# openSX70-dongle-USB-V2.net
KiCad netlist of a schematic drawn in EAGLE
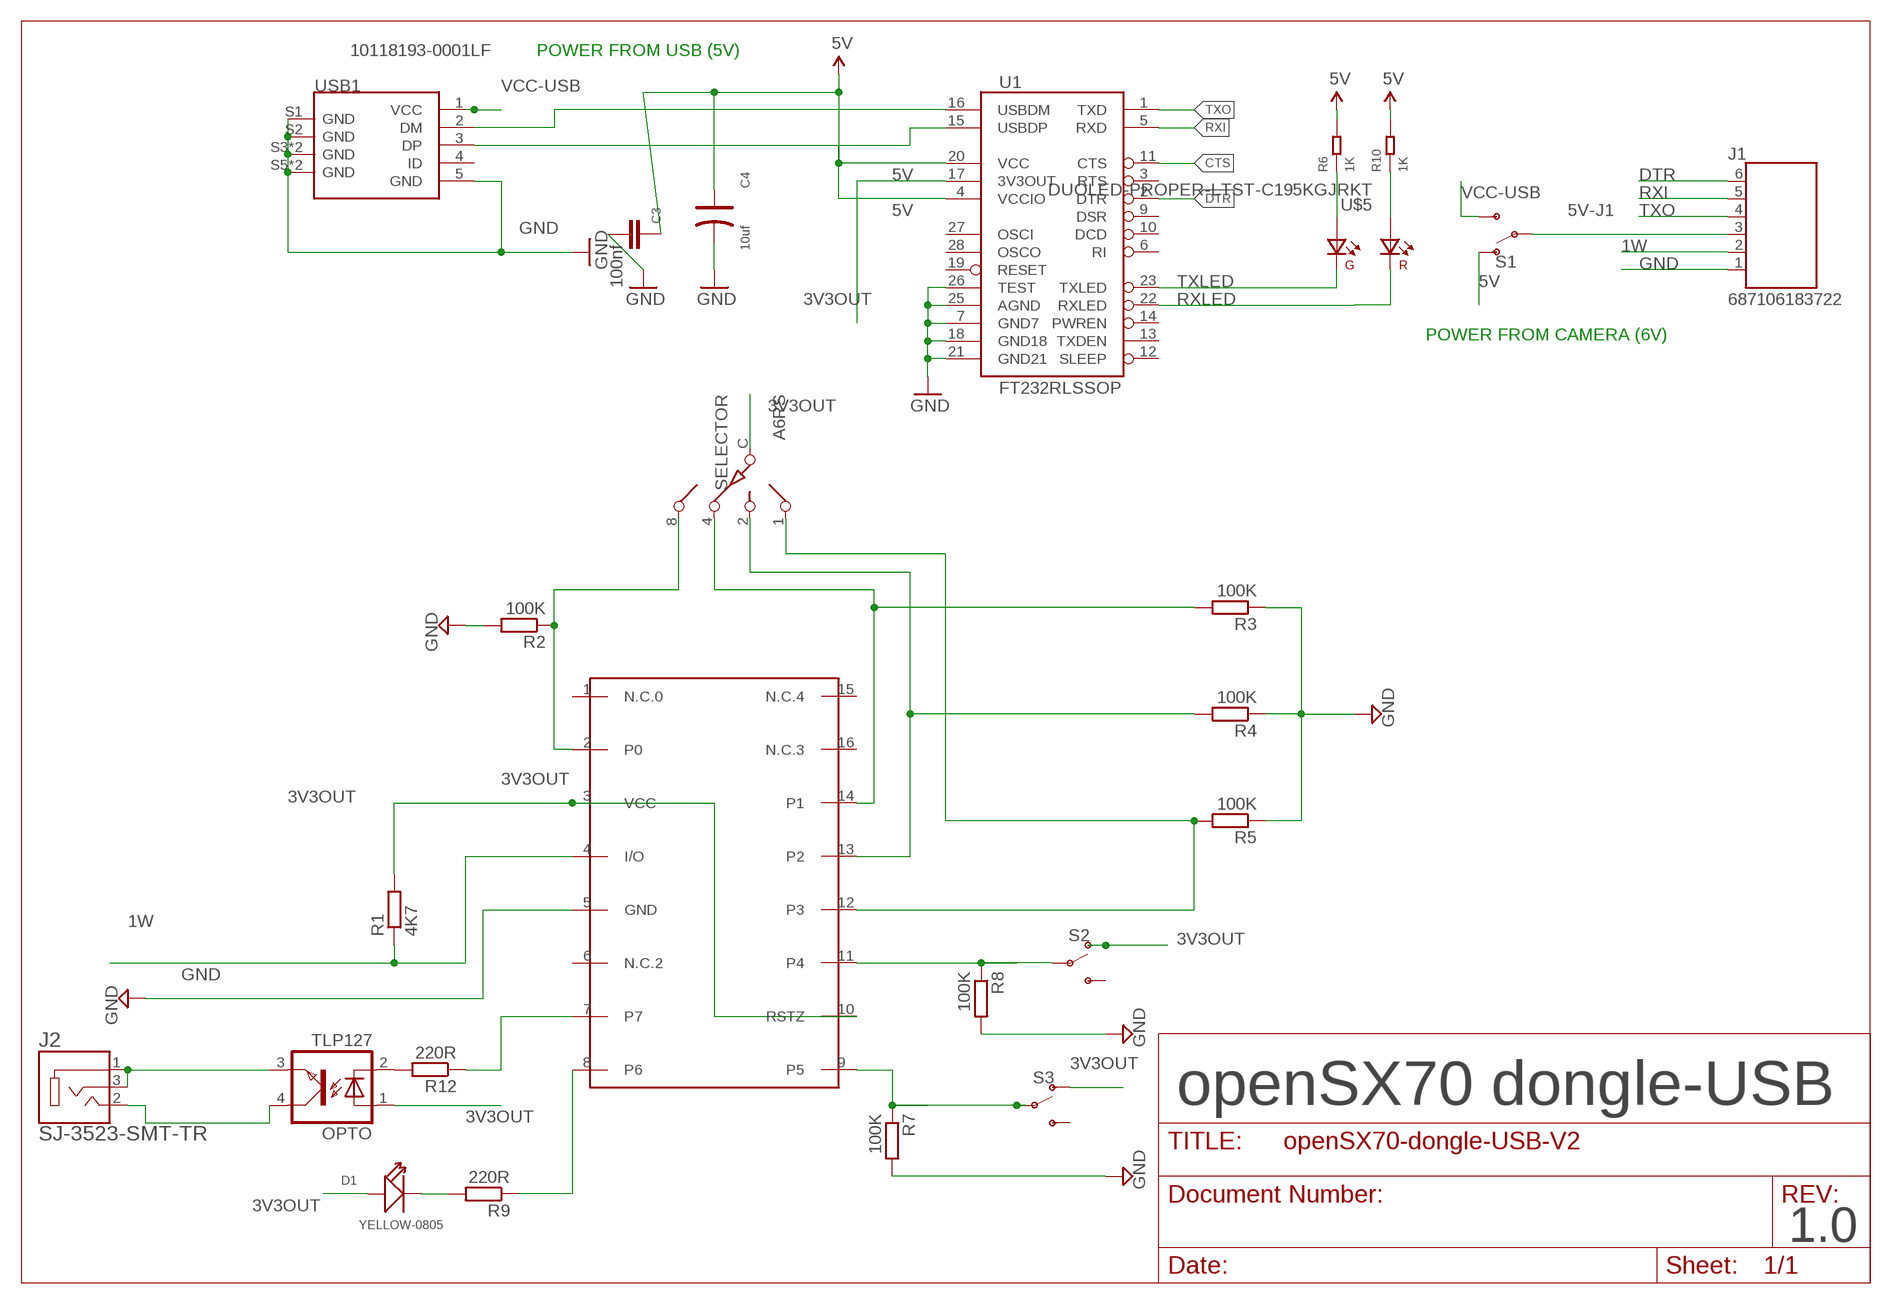
[diagram p0: schematic, sheet 1]

(export (version "E")
  (design (tool "Eeschema 10.0.6"))
  (components
    (comp (ref "C3")
      (value "100nf")
      (footprint "eagle-import:C0603")
      (libsource (lib "eagle-import") (part "C-EUC0603"))
    )
    (comp (ref "C4")
      (value "10uf")
      (footprint "eagle-import:AVX-A")
      (fields (field (name "MPN") "TAJA106K016RNJ"))
      (libsource (lib "eagle-import") (part "TANTALUM-SMD-10UF-16V-10%(AVX-A)"))
    )
    (comp (ref "D1")
      (value "YELLOW-0805")
      (footprint "eagle-import:LED-0805")
      (fields (field (name "MPN") "17-215UYC/S530-A3/TR8"))
      (libsource (lib "eagle-import") (part "SMD-LED-CLEAR-YELLOW(0805)"))
    )
    (comp (ref "DS2408")
      (value "DS2408")
      (footprint "eagle-import:SO16")
      (libsource (lib "eagle-import") (part "DS2408"))
    )
    (comp (ref "J1")
      (value "687106183722")
      (footprint "eagle-import:687106183722")
      (fields (field (name "MF") "Wurth Electronics"))
      (libsource (lib "eagle-import") (part "687106183722"))
    )
    (comp (ref "J2")
      (value "SJ-3523-SMT-TR")
      (footprint "eagle-import:CUI_SJ-3523-SMT-TR")
      (fields (field (name "MF") "CUI Inc."))
      (libsource (lib "eagle-import") (part "SJ-3523-SMT-TR"))
    )
    (comp (ref "OPTO")
      (value "TLP127")
      (footprint "eagle-import:SO-4")
      (libsource (lib "eagle-import") (part "TLP127"))
    )
    (comp (ref "R1")
      (value "4K7")
      (footprint "eagle-import:R0603")
      (libsource (lib "eagle-import") (part "R-EU_R0603"))
    )
    (comp (ref "R2")
      (value "100K")
      (footprint "eagle-import:R0603")
      (libsource (lib "eagle-import") (part "R-EU_R0603"))
    )
    (comp (ref "R3")
      (value "100K")
      (footprint "eagle-import:R0603")
      (libsource (lib "eagle-import") (part "R-EU_R0603"))
    )
    (comp (ref "R4")
      (value "100K")
      (footprint "eagle-import:R0603")
      (libsource (lib "eagle-import") (part "R-EU_R0603"))
    )
    (comp (ref "R5")
      (value "100K")
      (footprint "eagle-import:R0603")
      (libsource (lib "eagle-import") (part "R-EU_R0603"))
    )
    (comp (ref "R6")
      (value "1K")
      (footprint "eagle-import:R0603")
      (fields (field (name "MPN") "RC0603FR-071KL"))
      (libsource (lib "eagle-import") (part "SMD-RES-1K-1%-1/10W(0603)"))
    )
    (comp (ref "R7")
      (value "100K")
      (footprint "eagle-import:R0603")
      (libsource (lib "eagle-import") (part "R-EU_R0603"))
    )
    (comp (ref "R8")
      (value "100K")
      (footprint "eagle-import:R0603")
      (libsource (lib "eagle-import") (part "R-EU_R0603"))
    )
    (comp (ref "R9")
      (value "220R")
      (footprint "eagle-import:R0603")
      (libsource (lib "eagle-import") (part "R-EU_R0603"))
    )
    (comp (ref "R10")
      (value "1K")
      (footprint "eagle-import:R0603")
      (fields (field (name "MPN") "RC0603FR-071KL"))
      (libsource (lib "eagle-import") (part "SMD-RES-1K-1%-1/10W(0603)"))
    )
    (comp (ref "R12")
      (value "220R")
      (footprint "eagle-import:R0603")
      (libsource (lib "eagle-import") (part "R-EU_R0603"))
    )
    (comp (ref "S1")
      (value "SWITCH-SPDT-SMD-RIGHT-ANGLE")
      (footprint "eagle-import:SWITCH_SPST_SMD_A")
      (libsource (lib "eagle-import") (part "SWITCH-SPDT-SMD-RIGHT-ANGLE"))
    )
    (comp (ref "S2")
      (value "SWITCH-SPDT-SMD-RIGHT-ANGLE")
      (footprint "eagle-import:SWITCH_SPST_SMD_A")
      (libsource (lib "eagle-import") (part "SWITCH-SPDT-SMD-RIGHT-ANGLE"))
    )
    (comp (ref "S3")
      (value "SWITCH-SPDT-SMD-RIGHT-ANGLE")
      (footprint "eagle-import:SWITCH_SPST_SMD_A")
      (libsource (lib "eagle-import") (part "SWITCH-SPDT-SMD-RIGHT-ANGLE"))
    )
    (comp (ref "SELECTOR")
      (value "A6RS")
      (footprint "eagle-import:A6RS-161RS")
      (libsource (lib "eagle-import") (part "A6RS"))
    )
    (comp (ref "U$5")
      (value "DUOLED-PROPER-LTST-C195KGJRKT")
      (footprint "eagle-import:LTST-BILED-15X16")
      (fields (field (name "MF") "Lite-On Inc.") (field (name "MP") "LTST-C195KGJRKT"))
      (libsource (lib "eagle-import") (part "DUOLED-PROPER-LTST-C195KGJRKT"))
    )
    (comp (ref "U1")
      (value "FT232RLSSOP")
      (footprint "eagle-import:SSOP28DB")
      (libsource (lib "eagle-import") (part "FT232RLSSOP"))
    )
    (comp (ref "USB1")
      (value "10118193-0001LF")
      (footprint "eagle-import:MICRO-USB5+6P-SMD-0.65-B")
      (libsource (lib "eagle-import") (part "MICRO-USB-SMD-B-(10118193-0001LF)"))
    )
  )
  (nets
    (net (code "1") (name "/1W") (class "Default")
      (node (ref "DS2408") (pin "4") (pinfunction "I/O_4") (pintype "bidirectional"))
      (node (ref "J1") (pin "2") (pinfunction "5_2") (pintype "passive"))
      (node (ref "R1") (pin "1") (pinfunction "1_1") (pintype "passive"))
    )
    (net (code "2") (name "/3V3OUT") (class "Default")
      (node (ref "D1") (pin "+") (pinfunction "+_+") (pintype "passive"))
      (node (ref "DS2408") (pin "10") (pinfunction "RSTZ_10") (pintype "bidirectional"))
      (node (ref "DS2408") (pin "3") (pinfunction "VCC_3") (pintype "bidirectional"))
      (node (ref "OPTO") (pin "1") (pinfunction "A_1") (pintype "passive"))
      (node (ref "R1") (pin "2") (pinfunction "2_2") (pintype "passive"))
      (node (ref "S2") (pin "1") (pinfunction "O_1") (pintype "passive"))
      (node (ref "S3") (pin "1") (pinfunction "O_1") (pintype "passive"))
      (node (ref "SELECTOR") (pin "C") (pinfunction "C_C") (pintype "passive"))
      (node (ref "U1") (pin "17") (pinfunction "3V3OUT_17") (pintype "output"))
    )
    (net (code "3") (name "/5V-J1") (class "Default")
      (node (ref "J1") (pin "3") (pinfunction "4_3") (pintype "passive"))
      (node (ref "S1") (pin "2") (pinfunction "P_2") (pintype "passive"))
    )
    (net (code "4") (name "/RXLED") (class "Default")
      (node (ref "U$5") (pin "P$4") (pinfunction "K2_P$4") (pintype "passive"))
      (node (ref "U1") (pin "22") (pinfunction "RXLED_22") (pintype "input"))
    )
    (net (code "5") (name "/TXLED") (class "Default")
      (node (ref "U$5") (pin "P$3") (pinfunction "K1_P$3") (pintype "passive"))
      (node (ref "U1") (pin "23") (pinfunction "TXLED_23") (pintype "input"))
    )
    (net (code "6") (name "/VCC-USB") (class "Default")
      (node (ref "S1") (pin "3") (pinfunction "S_3") (pintype "passive"))
      (node (ref "USB1") (pin "1") (pinfunction "VCC_1") (pintype "bidirectional"))
    )
    (net (code "7") (name "5V") (class "Default")
      (node (ref "C3") (pin "1") (pinfunction "1_1") (pintype "passive"))
      (node (ref "C4") (pin "+") (pinfunction "+_+") (pintype "passive"))
      (node (ref "R10") (pin "2") (pinfunction "2_2") (pintype "passive"))
      (node (ref "R6") (pin "2") (pinfunction "2_2") (pintype "passive"))
      (node (ref "S1") (pin "1") (pinfunction "O_1") (pintype "passive"))
      (node (ref "U1") (pin "20") (pinfunction "VCC_20") (pintype "power_in"))
      (node (ref "U1") (pin "4") (pinfunction "VCCIO_4") (pintype "power_in"))
    )
    (net (code "8") (name "CTS") (class "Default")
      (node (ref "U1") (pin "11") (pinfunction "CTS_11") (pintype "input"))
    )
    (net (code "9") (name "DTR") (class "Default")
      (node (ref "J1") (pin "6") (pinfunction "1_6") (pintype "passive"))
      (node (ref "U1") (pin "2") (pinfunction "DTR_2") (pintype "output"))
    )
    (net (code "10") (name "GND") (class "Default")
      (node (ref "C3") (pin "2") (pinfunction "2_2") (pintype "passive"))
      (node (ref "C4") (pin "-") (pinfunction "-_-") (pintype "passive"))
      (node (ref "DS2408") (pin "5") (pinfunction "GND_5") (pintype "bidirectional"))
      (node (ref "J1") (pin "1") (pinfunction "6_1") (pintype "passive"))
      (node (ref "R2") (pin "2") (pinfunction "2_2") (pintype "passive"))
      (node (ref "R3") (pin "1") (pinfunction "1_1") (pintype "passive"))
      (node (ref "R4") (pin "1") (pinfunction "1_1") (pintype "passive"))
      (node (ref "R5") (pin "1") (pinfunction "1_1") (pintype "passive"))
      (node (ref "R7") (pin "2") (pinfunction "2_2") (pintype "passive"))
      (node (ref "R8") (pin "2") (pinfunction "2_2") (pintype "passive"))
      (node (ref "U1") (pin "18") (pinfunction "GND18_18") (pintype "power_in"))
      (node (ref "U1") (pin "21") (pinfunction "GND21_21") (pintype "power_in"))
      (node (ref "U1") (pin "25") (pinfunction "AGND_25") (pintype "power_in"))
      (node (ref "U1") (pin "26") (pinfunction "TEST_26") (pintype "input"))
      (node (ref "U1") (pin "7") (pinfunction "GND7_7") (pintype "power_in"))
      (node (ref "USB1") (pin "5") (pinfunction "GND_5") (pintype "bidirectional"))
      (node (ref "USB1") (pin "S1") (pinfunction "GND_S1") (pintype "bidirectional"))
      (node (ref "USB1") (pin "S2") (pinfunction "GND_S2") (pintype "bidirectional"))
      (node (ref "USB1") (pin "S3") (pinfunction "GND_S3") (pintype "bidirectional"))
      (node (ref "USB1") (pin "S4") (pinfunction "GND_S4") (pintype "bidirectional"))
      (node (ref "USB1") (pin "S5") (pinfunction "GND_S5") (pintype "bidirectional"))
      (node (ref "USB1") (pin "S6") (pinfunction "GND_S6") (pintype "bidirectional"))
    )
    (net (code "11") (name "Net-(D1-Pad-)") (class "Default")
      (node (ref "D1") (pin "-") (pinfunction "-_-") (pintype "passive"))
      (node (ref "R9") (pin "2") (pinfunction "2_2") (pintype "passive"))
    )
    (net (code "12") (name "Net-(DS2408-P0)") (class "Default")
      (node (ref "DS2408") (pin "2") (pinfunction "P0_2") (pintype "bidirectional"))
      (node (ref "R2") (pin "1") (pinfunction "1_1") (pintype "passive"))
      (node (ref "SELECTOR") (pin "8") (pinfunction "8_8") (pintype "passive"))
    )
    (net (code "13") (name "Net-(DS2408-P1)") (class "Default")
      (node (ref "DS2408") (pin "14") (pinfunction "P1_14") (pintype "bidirectional"))
      (node (ref "R3") (pin "2") (pinfunction "2_2") (pintype "passive"))
      (node (ref "SELECTOR") (pin "4") (pinfunction "4_4") (pintype "passive"))
    )
    (net (code "14") (name "Net-(DS2408-P2)") (class "Default")
      (node (ref "DS2408") (pin "13") (pinfunction "P2_13") (pintype "bidirectional"))
      (node (ref "R4") (pin "2") (pinfunction "2_2") (pintype "passive"))
      (node (ref "SELECTOR") (pin "2") (pinfunction "2_2") (pintype "passive"))
    )
    (net (code "15") (name "Net-(DS2408-P3)") (class "Default")
      (node (ref "DS2408") (pin "12") (pinfunction "P3_12") (pintype "bidirectional"))
      (node (ref "R5") (pin "2") (pinfunction "2_2") (pintype "passive"))
      (node (ref "SELECTOR") (pin "1") (pinfunction "1_1") (pintype "passive"))
    )
    (net (code "16") (name "Net-(DS2408-P4)") (class "Default")
      (node (ref "DS2408") (pin "11") (pinfunction "P4_11") (pintype "bidirectional"))
      (node (ref "R8") (pin "1") (pinfunction "1_1") (pintype "passive"))
      (node (ref "S2") (pin "2") (pinfunction "P_2") (pintype "passive"))
    )
    (net (code "17") (name "Net-(DS2408-P5)") (class "Default")
      (node (ref "DS2408") (pin "9") (pinfunction "P5_9") (pintype "bidirectional"))
      (node (ref "R7") (pin "1") (pinfunction "1_1") (pintype "passive"))
      (node (ref "S3") (pin "2") (pinfunction "P_2") (pintype "passive"))
    )
    (net (code "18") (name "Net-(DS2408-P6)") (class "Default")
      (node (ref "DS2408") (pin "8") (pinfunction "P6_8") (pintype "bidirectional"))
      (node (ref "R9") (pin "1") (pinfunction "1_1") (pintype "passive"))
    )
    (net (code "19") (name "Net-(DS2408-P7)") (class "Default")
      (node (ref "DS2408") (pin "7") (pinfunction "P7_7") (pintype "bidirectional"))
      (node (ref "R12") (pin "1") (pinfunction "1_1") (pintype "passive"))
    )
    (net (code "20") (name "Net-(OPTO-C)") (class "Default")
      (node (ref "OPTO") (pin "2") (pinfunction "C_2") (pintype "passive"))
      (node (ref "R12") (pin "2") (pinfunction "2_2") (pintype "passive"))
    )
    (net (code "21") (name "Net-(OPTO-COL)") (class "Default")
      (node (ref "J2") (pin "2") (pinfunction "2_2") (pintype "passive"))
      (node (ref "OPTO") (pin "4") (pinfunction "COL_4") (pintype "passive"))
    )
    (net (code "22") (name "Net-(OPTO-EMIT)") (class "Default")
      (node (ref "J2") (pin "1") (pinfunction "1_1") (pintype "passive"))
      (node (ref "J2") (pin "3") (pinfunction "3_3") (pintype "passive"))
      (node (ref "OPTO") (pin "3") (pinfunction "EMIT_3") (pintype "passive"))
    )
    (net (code "23") (name "Net-(U$5-A1)") (class "Default")
      (node (ref "R6") (pin "1") (pinfunction "1_1") (pintype "passive"))
      (node (ref "U$5") (pin "P$1") (pinfunction "A1_P$1") (pintype "passive"))
    )
    (net (code "24") (name "Net-(U$5-A2)") (class "Default")
      (node (ref "R10") (pin "1") (pinfunction "1_1") (pintype "passive"))
      (node (ref "U$5") (pin "P$2") (pinfunction "A2_P$2") (pintype "passive"))
    )
    (net (code "25") (name "Net-(U1-USBDM)") (class "Default")
      (node (ref "U1") (pin "16") (pinfunction "USBDM_16") (pintype "bidirectional"))
      (node (ref "USB1") (pin "2") (pinfunction "DM_2") (pintype "bidirectional"))
    )
    (net (code "26") (name "Net-(U1-USBDP)") (class "Default")
      (node (ref "U1") (pin "15") (pinfunction "USBDP_15") (pintype "bidirectional"))
      (node (ref "USB1") (pin "3") (pinfunction "DP_3") (pintype "bidirectional"))
    )
    (net (code "27") (name "RXI") (class "Default")
      (node (ref "J1") (pin "5") (pinfunction "2_5") (pintype "passive"))
      (node (ref "U1") (pin "5") (pinfunction "RXD_5") (pintype "input"))
    )
    (net (code "28") (name "TXO") (class "Default")
      (node (ref "J1") (pin "4") (pinfunction "3_4") (pintype "passive"))
      (node (ref "U1") (pin "1") (pinfunction "TXD_1") (pintype "output"))
    )
    (net (code "29") (name "unconnected-(DS2408-N.C.0-Pad1)") (class "Default")
      (node (ref "DS2408") (pin "1") (pinfunction "N.C.0_1") (pintype "bidirectional"))
    )
    (net (code "30") (name "unconnected-(DS2408-N.C.2-Pad6)") (class "Default")
      (node (ref "DS2408") (pin "6") (pinfunction "N.C.2_6") (pintype "bidirectional"))
    )
    (net (code "31") (name "unconnected-(DS2408-N.C.3-Pad16)") (class "Default")
      (node (ref "DS2408") (pin "16") (pinfunction "N.C.3_16") (pintype "bidirectional"))
    )
    (net (code "32") (name "unconnected-(DS2408-N.C.4-Pad15)") (class "Default")
      (node (ref "DS2408") (pin "15") (pinfunction "N.C.4_15") (pintype "bidirectional"))
    )
    (net (code "33") (name "unconnected-(S2-S-Pad3)") (class "Default")
      (node (ref "S2") (pin "3") (pinfunction "S_3") (pintype "passive"))
    )
    (net (code "34") (name "unconnected-(S3-S-Pad3)") (class "Default")
      (node (ref "S3") (pin "3") (pinfunction "S_3") (pintype "passive"))
    )
    (net (code "35") (name "unconnected-(U1-DCD-Pad10)") (class "Default")
      (node (ref "U1") (pin "10") (pinfunction "DCD_10") (pintype "input"))
    )
    (net (code "36") (name "unconnected-(U1-DSR-Pad9)") (class "Default")
      (node (ref "U1") (pin "9") (pinfunction "DSR_9") (pintype "input"))
    )
    (net (code "37") (name "unconnected-(U1-OSCI-Pad27)") (class "Default")
      (node (ref "U1") (pin "27") (pinfunction "OSCI_27") (pintype "input"))
    )
    (net (code "38") (name "unconnected-(U1-OSCO-Pad28)") (class "Default")
      (node (ref "U1") (pin "28") (pinfunction "OSCO_28") (pintype "output"))
    )
    (net (code "39") (name "unconnected-(U1-PWREN-Pad14)") (class "Default")
      (node (ref "U1") (pin "14") (pinfunction "PWREN_14") (pintype "input"))
    )
    (net (code "40") (name "unconnected-(U1-RESET-Pad19)") (class "Default")
      (node (ref "U1") (pin "19") (pinfunction "RESET_19") (pintype "input"))
    )
    (net (code "41") (name "unconnected-(U1-RI-Pad6)") (class "Default")
      (node (ref "U1") (pin "6") (pinfunction "RI_6") (pintype "input"))
    )
    (net (code "42") (name "unconnected-(U1-RTS-Pad3)") (class "Default")
      (node (ref "U1") (pin "3") (pinfunction "RTS_3") (pintype "output"))
    )
    (net (code "43") (name "unconnected-(U1-SLEEP-Pad12)") (class "Default")
      (node (ref "U1") (pin "12") (pinfunction "SLEEP_12") (pintype "input"))
    )
    (net (code "44") (name "unconnected-(U1-TXDEN-Pad13)") (class "Default")
      (node (ref "U1") (pin "13") (pinfunction "TXDEN_13") (pintype "input"))
    )
    (net (code "45") (name "unconnected-(USB1-ID-Pad4)") (class "Default")
      (node (ref "USB1") (pin "4") (pinfunction "ID_4") (pintype "bidirectional"))
    )
  )
)
